# tractor_2v4.net
KiCad netlist of a schematic drawn in EAGLE
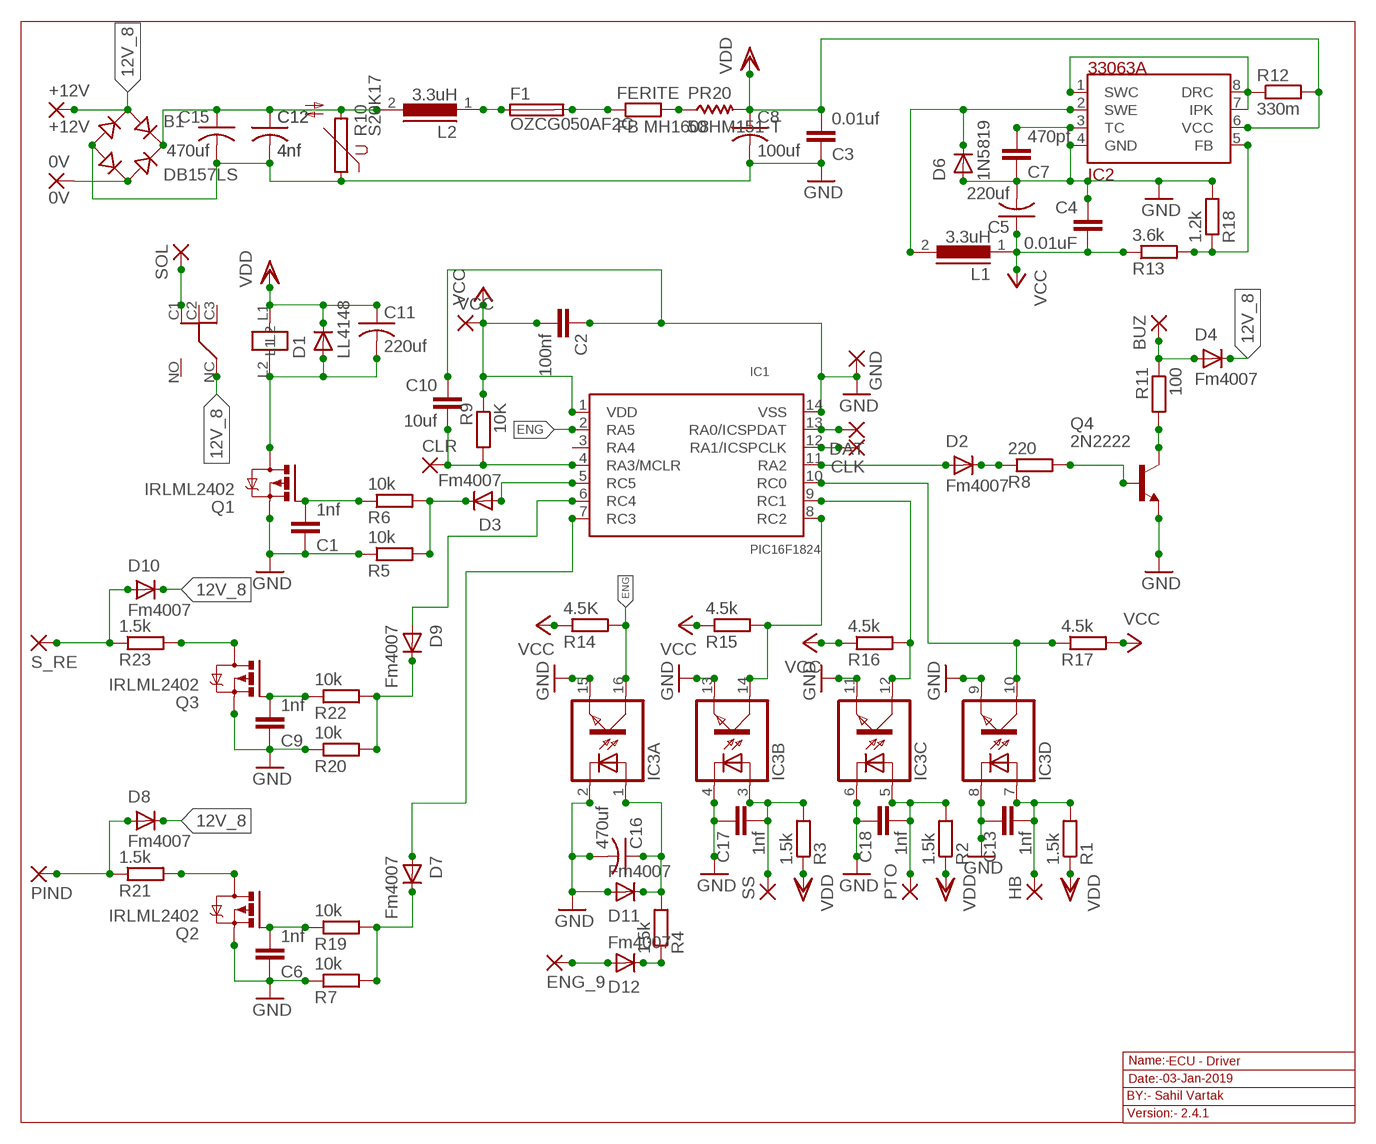
[diagram p0: schematic, sheet 1]

(export (version "E")
  (design (tool "Eeschema 10.0.6"))
  (components
    (comp (ref "+12V")
      (value "+12V")
      (footprint "eagle-import:2,54_1,1")
      (libsource (lib "eagle-import") (part "2,54/1,1"))
    )
    (comp (ref "0V")
      (value "0V")
      (footprint "eagle-import:2,54_1,1")
      (libsource (lib "eagle-import") (part "2,54/1,1"))
    )
    (comp (ref "B1")
      (value "DB157LS")
      (footprint "eagle-import:DBS")
      (libsource (lib "eagle-import") (part "DB?GS106"))
    )
    (comp (ref "BUZ")
      (value "2,54/1,1")
      (footprint "eagle-import:2,54_1,1")
      (libsource (lib "eagle-import") (part "2,54/1,1"))
    )
    (comp (ref "C1")
      (value "1nf")
      (footprint "eagle-import:C0603")
      (libsource (lib "eagle-import") (part "CC0603"))
    )
    (comp (ref "C2")
      (value "100nf")
      (footprint "eagle-import:C0603")
      (libsource (lib "eagle-import") (part "CC0603"))
    )
    (comp (ref "C3")
      (value "0.01uf")
      (footprint "eagle-import:C0603")
      (libsource (lib "eagle-import") (part "CC0603"))
    )
    (comp (ref "C4")
      (value "0.01uF")
      (footprint "eagle-import:C0603")
      (libsource (lib "eagle-import") (part "CC0603"))
    )
    (comp (ref "C5")
      (value "220uf")
      (footprint "eagle-import:C025-025X050")
      (libsource (lib "eagle-import") (part "C-US025-025X050"))
    )
    (comp (ref "C6")
      (value "1nf")
      (footprint "eagle-import:C0603")
      (libsource (lib "eagle-import") (part "CC0603"))
    )
    (comp (ref "C7")
      (value "470pf")
      (footprint "eagle-import:C0603")
      (libsource (lib "eagle-import") (part "CC0603"))
    )
    (comp (ref "C8")
      (value "100uf")
      (footprint "eagle-import:C025-025X050")
      (libsource (lib "eagle-import") (part "C-US025-025X050"))
    )
    (comp (ref "C9")
      (value "1nf")
      (footprint "eagle-import:C0603")
      (libsource (lib "eagle-import") (part "CC0603"))
    )
    (comp (ref "C10")
      (value "10uf")
      (footprint "eagle-import:C0603")
      (libsource (lib "eagle-import") (part "CC0603"))
    )
    (comp (ref "C11")
      (value "220uf")
      (footprint "eagle-import:C025-025X050")
      (libsource (lib "eagle-import") (part "C-US025-025X050"))
    )
    (comp (ref "C12")
      (value "4nf")
      (footprint "eagle-import:C050-045X075")
      (libsource (lib "eagle-import") (part "C-US050-045X075"))
    )
    (comp (ref "C13")
      (value "1nf")
      (footprint "eagle-import:C0603")
      (libsource (lib "eagle-import") (part "CC0603"))
    )
    (comp (ref "C15")
      (value "470uf")
      (footprint "eagle-import:C050-075X075")
      (libsource (lib "eagle-import") (part "resistor_C-US050-075X075"))
    )
    (comp (ref "C16")
      (value "470uf")
      (footprint "eagle-import:C050-075X075")
      (libsource (lib "eagle-import") (part "resistor_C-US050-075X075"))
    )
    (comp (ref "C17")
      (value "1nf")
      (footprint "eagle-import:C0603")
      (libsource (lib "eagle-import") (part "CC0603"))
    )
    (comp (ref "C18")
      (value "1nf")
      (footprint "eagle-import:C0603")
      (libsource (lib "eagle-import") (part "CC0603"))
    )
    (comp (ref "CLK")
      (value "1,6/0,8")
      (footprint "eagle-import:1,6_0,8")
      (libsource (lib "eagle-import") (part "1,6/0,8"))
    )
    (comp (ref "CLR")
      (value "1,6/0,8")
      (footprint "eagle-import:1,6_0,8")
      (libsource (lib "eagle-import") (part "1,6/0,8"))
    )
    (comp (ref "D1")
      (value "LL4148")
      (footprint "eagle-import:SMA-DO214AC")
      (libsource (lib "eagle-import") (part "GF1"))
    )
    (comp (ref "D2")
      (value "Fm4007")
      (footprint "eagle-import:SMA-DO214AC")
      (libsource (lib "eagle-import") (part "GF1"))
    )
    (comp (ref "D3")
      (value "Fm4007")
      (footprint "eagle-import:SMA-DO214AC")
      (libsource (lib "eagle-import") (part "GF1"))
    )
    (comp (ref "D4")
      (value "Fm4007")
      (footprint "eagle-import:SMA-DO214AC")
      (libsource (lib "eagle-import") (part "GF1"))
    )
    (comp (ref "D6")
      (value "1N5819")
      (footprint "eagle-import:SMA-DO214AC")
      (libsource (lib "eagle-import") (part "GF1"))
    )
    (comp (ref "D7")
      (value "Fm4007")
      (footprint "eagle-import:SMA-DO214AC")
      (libsource (lib "eagle-import") (part "GF1"))
    )
    (comp (ref "D8")
      (value "Fm4007")
      (footprint "eagle-import:SMA-DO214AC")
      (libsource (lib "eagle-import") (part "GF1"))
    )
    (comp (ref "D9")
      (value "Fm4007")
      (footprint "eagle-import:SMA-DO214AC")
      (libsource (lib "eagle-import") (part "GF1"))
    )
    (comp (ref "D10")
      (value "Fm4007")
      (footprint "eagle-import:SMA-DO214AC")
      (libsource (lib "eagle-import") (part "GF1"))
    )
    (comp (ref "D11")
      (value "Fm4007")
      (footprint "eagle-import:SMA-DO214AC")
      (libsource (lib "eagle-import") (part "GF1"))
    )
    (comp (ref "D12")
      (value "Fm4007")
      (footprint "eagle-import:SMA-DO214AC")
      (libsource (lib "eagle-import") (part "GF1"))
    )
    (comp (ref "DAT")
      (value "1,6/0,8")
      (footprint "eagle-import:1,6_0,8")
      (libsource (lib "eagle-import") (part "1,6/0,8"))
    )
    (comp (ref "ENG_9")
      (value "2,54/1,1")
      (footprint "eagle-import:2,54_1,1")
      (libsource (lib "eagle-import") (part "2,54/1,1"))
    )
    (comp (ref "F1")
      (value "OZCG050AF2C")
      (footprint "eagle-import:RES_FUSE")
      (libsource (lib "eagle-import") (part "RES_FUSE"))
    )
    (comp (ref "FERITE")
      (value "FB MH1608HM151-T")
      (footprint "eagle-import:R0603")
      (libsource (lib "eagle-import") (part "R-EU_R0603"))
    )
    (comp (ref "GND")
      (value "1,6/0,8")
      (footprint "eagle-import:1,6_0,8")
      (libsource (lib "eagle-import") (part "1,6/0,8"))
    )
    (comp (ref "HB")
      (value "2,54/1,1")
      (footprint "eagle-import:2,54_1,1")
      (libsource (lib "eagle-import") (part "2,54/1,1"))
    )
    (comp (ref "IC1")
      (value "PIC16F1824")
      (footprint "eagle-import:SO-14")
      (libsource (lib "eagle-import") (part "PIC16F1824"))
    )
    (comp (ref "IC2")
      (value "33063A")
      (footprint "eagle-import:D_R-PDSO-G8")
      (libsource (lib "eagle-import") (part "33063A"))
    )
    (comp (ref "IC3")
      (value "TLP283-4")
      (footprint "eagle-import:MINI-FLAT-16")
      (libsource (lib "eagle-import") (part "TLP283-4"))
    )
    (comp (ref "K2")
      (value "RL3531RL3")
      (footprint "eagle-import:RL3531")
      (libsource (lib "eagle-import") (part "RL3531RL3"))
    )
    (comp (ref "L1")
      (value "3.3uH")
      (footprint "eagle-import:82114R")
      (libsource (lib "eagle-import") (part "82114R"))
    )
    (comp (ref "L2")
      (value "3.3uH")
      (footprint "eagle-import:82114R")
      (libsource (lib "eagle-import") (part "82114R"))
    )
    (comp (ref "PIND")
      (value "2,54/1,1")
      (footprint "eagle-import:2,54_1,1")
      (libsource (lib "eagle-import") (part "2,54/1,1"))
    )
    (comp (ref "PR20")
      (value "50")
      (footprint "eagle-import:WSC2515")
      (libsource (lib "eagle-import") (part "R-US_WSC2515"))
    )
    (comp (ref "PTO")
      (value "2,54/1,1")
      (footprint "eagle-import:2,54_1,1")
      (libsource (lib "eagle-import") (part "2,54/1,1"))
    )
    (comp (ref "Q1")
      (value "IRLML2402")
      (footprint "eagle-import:MICRO3")
      (libsource (lib "eagle-import") (part "IRLML5203"))
    )
    (comp (ref "Q2")
      (value "IRLML2402")
      (footprint "eagle-import:MICRO3")
      (libsource (lib "eagle-import") (part "IRLML5203"))
    )
    (comp (ref "Q3")
      (value "IRLML2402")
      (footprint "eagle-import:MICRO3")
      (libsource (lib "eagle-import") (part "IRLML5203"))
    )
    (comp (ref "Q4")
      (value "2N2222")
      (footprint "eagle-import:TO18")
      (libsource (lib "eagle-import") (part "2N2222"))
    )
    (comp (ref "R1")
      (value "1.5k")
      (footprint "eagle-import:R0603")
      (libsource (lib "eagle-import") (part "RR0603"))
    )
    (comp (ref "R2")
      (value "1.5k")
      (footprint "eagle-import:R0603")
      (libsource (lib "eagle-import") (part "RR0603"))
    )
    (comp (ref "R3")
      (value "1.5k")
      (footprint "eagle-import:R0603")
      (libsource (lib "eagle-import") (part "RR0603"))
    )
    (comp (ref "R4")
      (value "1.5k")
      (footprint "eagle-import:R0603")
      (libsource (lib "eagle-import") (part "RR0603"))
    )
    (comp (ref "R5")
      (value "10k")
      (footprint "eagle-import:R0603")
      (libsource (lib "eagle-import") (part "RR0603"))
    )
    (comp (ref "R6")
      (value "10k")
      (footprint "eagle-import:R0603")
      (libsource (lib "eagle-import") (part "RR0603"))
    )
    (comp (ref "R7")
      (value "10k")
      (footprint "eagle-import:R0603")
      (libsource (lib "eagle-import") (part "RR0603"))
    )
    (comp (ref "R8")
      (value "220")
      (footprint "eagle-import:R0603")
      (libsource (lib "eagle-import") (part "RR0603"))
    )
    (comp (ref "R9")
      (value "10K")
      (footprint "eagle-import:R0603")
      (libsource (lib "eagle-import") (part "RR0603"))
    )
    (comp (ref "R10")
      (value "S20K17")
      (footprint "eagle-import:S14K17")
      (libsource (lib "eagle-import") (part "S14K17"))
    )
    (comp (ref "R11")
      (value "100")
      (footprint "eagle-import:R0603")
      (libsource (lib "eagle-import") (part "RR0603"))
    )
    (comp (ref "R12")
      (value "330m")
      (footprint "eagle-import:R2010")
      (libsource (lib "eagle-import") (part "RR2010"))
    )
    (comp (ref "R13")
      (value "3.6k")
      (footprint "eagle-import:R0603")
      (libsource (lib "eagle-import") (part "RR0603"))
    )
    (comp (ref "R14")
      (value "4.5K")
      (footprint "eagle-import:R0603")
      (libsource (lib "eagle-import") (part "RR0603"))
    )
    (comp (ref "R15")
      (value "4.5k")
      (footprint "eagle-import:R0603")
      (libsource (lib "eagle-import") (part "RR0603"))
    )
    (comp (ref "R16")
      (value "4.5k")
      (footprint "eagle-import:R0603")
      (libsource (lib "eagle-import") (part "RR0603"))
    )
    (comp (ref "R17")
      (value "4.5k")
      (footprint "eagle-import:R0603")
      (libsource (lib "eagle-import") (part "RR0603"))
    )
    (comp (ref "R18")
      (value "1.2k")
      (footprint "eagle-import:R0603")
      (libsource (lib "eagle-import") (part "RR0603"))
    )
    (comp (ref "R19")
      (value "10k")
      (footprint "eagle-import:R0603")
      (libsource (lib "eagle-import") (part "RR0603"))
    )
    (comp (ref "R20")
      (value "10k")
      (footprint "eagle-import:R0603")
      (libsource (lib "eagle-import") (part "RR0603"))
    )
    (comp (ref "R21")
      (value "1.5k")
      (footprint "eagle-import:R0603")
      (libsource (lib "eagle-import") (part "RR0603"))
    )
    (comp (ref "R22")
      (value "10k")
      (footprint "eagle-import:R0603")
      (libsource (lib "eagle-import") (part "RR0603"))
    )
    (comp (ref "R23")
      (value "1.5k")
      (footprint "eagle-import:R0603")
      (libsource (lib "eagle-import") (part "RR0603"))
    )
    (comp (ref "SOL")
      (value "2,54/1,1")
      (footprint "eagle-import:2,54_1,1")
      (libsource (lib "eagle-import") (part "2,54/1,1"))
    )
    (comp (ref "SS")
      (value "2,54/1,1")
      (footprint "eagle-import:2,54_1,1")
      (libsource (lib "eagle-import") (part "2,54/1,1"))
    )
    (comp (ref "S_RE")
      (value "2,54/1,1")
      (footprint "eagle-import:2,54_1,1")
      (libsource (lib "eagle-import") (part "2,54/1,1"))
    )
    (comp (ref "VCC")
      (value "1,6/0,8")
      (footprint "eagle-import:1,6_0,8")
      (libsource (lib "eagle-import") (part "1,6/0,8"))
    )
  )
  (nets
    (net (code "1") (name "12V_8") (class "Default")
      (node (ref "+12V") (pin "1") (pinfunction "P_1") (pintype "passive"))
      (node (ref "B1") (pin "AC1") (pinfunction "AC1_AC1") (pintype "passive"))
      (node (ref "D10") (pin "K") (pinfunction "C_K") (pintype "passive"))
      (node (ref "D4") (pin "K") (pinfunction "C_K") (pintype "passive"))
      (node (ref "D8") (pin "K") (pinfunction "C_K") (pintype "passive"))
      (node (ref "K2") (pin "NC") (pinfunction "NC_NC") (pintype "output"))
    )
    (net (code "2") (name "ENG") (class "Default")
      (node (ref "IC1") (pin "2") (pinfunction "RA5_2") (pintype "bidirectional"))
      (node (ref "IC3") (pin "16") (pinfunction "COL_16") (pintype "passive"))
      (node (ref "R14") (pin "2") (pinfunction "2_2") (pintype "passive"))
    )
    (net (code "3") (name "GND") (class "Default")
      (node (ref "B1") (pin "-") (pinfunction "-_-") (pintype "passive"))
      (node (ref "C1") (pin "1") (pinfunction "1_1") (pintype "passive"))
      (node (ref "C10") (pin "1") (pinfunction "1_1") (pintype "passive"))
      (node (ref "C12") (pin "2") (pinfunction "2_2") (pintype "passive"))
      (node (ref "C13") (pin "1") (pinfunction "1_1") (pintype "passive"))
      (node (ref "C15") (pin "2") (pinfunction "2_2") (pintype "passive"))
      (node (ref "C16") (pin "2") (pinfunction "2_2") (pintype "passive"))
      (node (ref "C17") (pin "1") (pinfunction "1_1") (pintype "passive"))
      (node (ref "C18") (pin "1") (pinfunction "1_1") (pintype "passive"))
      (node (ref "C2") (pin "1") (pinfunction "1_1") (pintype "passive"))
      (node (ref "C3") (pin "1") (pinfunction "1_1") (pintype "passive"))
      (node (ref "C4") (pin "1") (pinfunction "1_1") (pintype "passive"))
      (node (ref "C5") (pin "2") (pinfunction "2_2") (pintype "passive"))
      (node (ref "C6") (pin "1") (pinfunction "1_1") (pintype "passive"))
      (node (ref "C7") (pin "1") (pinfunction "1_1") (pintype "passive"))
      (node (ref "C8") (pin "2") (pinfunction "2_2") (pintype "passive"))
      (node (ref "C9") (pin "1") (pinfunction "1_1") (pintype "passive"))
      (node (ref "D11") (pin "A") (pinfunction "A_A") (pintype "passive"))
      (node (ref "D6") (pin "A") (pinfunction "A_A") (pintype "passive"))
      (node (ref "GND") (pin "1") (pinfunction "P_1") (pintype "passive"))
      (node (ref "IC1") (pin "14") (pinfunction "VSS_14") (pintype "bidirectional"))
      (node (ref "IC2") (pin "4") (pinfunction "GND_4") (pintype "bidirectional"))
      (node (ref "IC3") (pin "11") (pinfunction "EMIT_11") (pintype "passive"))
      (node (ref "IC3") (pin "13") (pinfunction "EMIT_13") (pintype "passive"))
      (node (ref "IC3") (pin "15") (pinfunction "EMIT_15") (pintype "passive"))
      (node (ref "IC3") (pin "2") (pinfunction "C_2") (pintype "passive"))
      (node (ref "IC3") (pin "4") (pinfunction "C_4") (pintype "passive"))
      (node (ref "IC3") (pin "6") (pinfunction "C_6") (pintype "passive"))
      (node (ref "IC3") (pin "8") (pinfunction "C_8") (pintype "passive"))
      (node (ref "IC3") (pin "9") (pinfunction "EMIT_9") (pintype "passive"))
      (node (ref "Q1") (pin "2") (pinfunction "S_2") (pintype "passive"))
      (node (ref "Q2") (pin "2") (pinfunction "S_2") (pintype "passive"))
      (node (ref "Q3") (pin "2") (pinfunction "S_2") (pintype "passive"))
      (node (ref "Q4") (pin "1") (pinfunction "E_1") (pintype "passive"))
      (node (ref "R10") (pin "1") (pinfunction "1_1") (pintype "passive"))
      (node (ref "R18") (pin "2") (pinfunction "2_2") (pintype "passive"))
      (node (ref "R20") (pin "1") (pinfunction "1_1") (pintype "passive"))
      (node (ref "R5") (pin "1") (pinfunction "1_1") (pintype "passive"))
      (node (ref "R7") (pin "1") (pinfunction "1_1") (pintype "passive"))
    )
    (net (code "4") (name "Net-(0V-P)") (class "Default")
      (node (ref "0V") (pin "1") (pinfunction "P_1") (pintype "passive"))
      (node (ref "B1") (pin "AC2") (pinfunction "AC2_AC2") (pintype "passive"))
    )
    (net (code "5") (name "Net-(B1-Pad+)") (class "Default")
      (node (ref "B1") (pin "+") (pinfunction "+_+") (pintype "passive"))
      (node (ref "C12") (pin "1") (pinfunction "1_1") (pintype "passive"))
      (node (ref "C15") (pin "1") (pinfunction "1_1") (pintype "passive"))
      (node (ref "L2") (pin "2") (pinfunction "2_2") (pintype "passive"))
      (node (ref "R10") (pin "2") (pinfunction "2_2") (pintype "passive"))
    )
    (net (code "6") (name "Net-(BUZ-P)") (class "Default")
      (node (ref "BUZ") (pin "1") (pinfunction "P_1") (pintype "passive"))
      (node (ref "D4") (pin "A") (pinfunction "A_A") (pintype "passive"))
      (node (ref "R11") (pin "1") (pinfunction "1_1") (pintype "passive"))
    )
    (net (code "7") (name "Net-(CLK-P)") (class "Default")
      (node (ref "CLK") (pin "1") (pinfunction "P_1") (pintype "passive"))
      (node (ref "IC1") (pin "12") (pinfunction "RA1/ICSPCLK_12") (pintype "bidirectional"))
    )
    (net (code "8") (name "Net-(CLR-P)") (class "Default")
      (node (ref "C10") (pin "2") (pinfunction "2_2") (pintype "passive"))
      (node (ref "CLR") (pin "1") (pinfunction "P_1") (pintype "passive"))
      (node (ref "IC1") (pin "4") (pinfunction "RA3/MCLR_4") (pintype "bidirectional"))
      (node (ref "R9") (pin "2") (pinfunction "2_2") (pintype "passive"))
    )
    (net (code "9") (name "Net-(D2-C)") (class "Default")
      (node (ref "D2") (pin "K") (pinfunction "C_K") (pintype "passive"))
      (node (ref "R8") (pin "1") (pinfunction "1_1") (pintype "passive"))
    )
    (net (code "10") (name "Net-(D3-C)") (class "Default")
      (node (ref "D3") (pin "K") (pinfunction "C_K") (pintype "passive"))
      (node (ref "R5") (pin "2") (pinfunction "2_2") (pintype "passive"))
      (node (ref "R6") (pin "2") (pinfunction "2_2") (pintype "passive"))
    )
    (net (code "11") (name "Net-(D6-C)") (class "Default")
      (node (ref "D6") (pin "K") (pinfunction "C_K") (pintype "passive"))
      (node (ref "IC2") (pin "2") (pinfunction "SWE_2") (pintype "bidirectional"))
      (node (ref "L1") (pin "2") (pinfunction "2_2") (pintype "passive"))
    )
    (net (code "12") (name "Net-(D7-C)") (class "Default")
      (node (ref "D7") (pin "K") (pinfunction "C_K") (pintype "passive"))
      (node (ref "R19") (pin "2") (pinfunction "2_2") (pintype "passive"))
      (node (ref "R7") (pin "2") (pinfunction "2_2") (pintype "passive"))
    )
    (net (code "13") (name "Net-(D9-C)") (class "Default")
      (node (ref "D9") (pin "K") (pinfunction "C_K") (pintype "passive"))
      (node (ref "R20") (pin "2") (pinfunction "2_2") (pintype "passive"))
      (node (ref "R22") (pin "2") (pinfunction "2_2") (pintype "passive"))
    )
    (net (code "14") (name "Net-(D11-C)") (class "Default")
      (node (ref "C16") (pin "1") (pinfunction "1_1") (pintype "passive"))
      (node (ref "D11") (pin "K") (pinfunction "C_K") (pintype "passive"))
      (node (ref "IC3") (pin "1") (pinfunction "A_1") (pintype "passive"))
      (node (ref "R4") (pin "2") (pinfunction "2_2") (pintype "passive"))
    )
    (net (code "15") (name "Net-(D12-C)") (class "Default")
      (node (ref "D12") (pin "K") (pinfunction "C_K") (pintype "passive"))
      (node (ref "R4") (pin "1") (pinfunction "1_1") (pintype "passive"))
    )
    (net (code "16") (name "Net-(DAT-P)") (class "Default")
      (node (ref "DAT") (pin "1") (pinfunction "P_1") (pintype "passive"))
      (node (ref "IC1") (pin "13") (pinfunction "RA0/ICSPDAT_13") (pintype "bidirectional"))
    )
    (net (code "17") (name "Net-(ENG_9-P)") (class "Default")
      (node (ref "D12") (pin "A") (pinfunction "A_A") (pintype "passive"))
      (node (ref "ENG_9") (pin "1") (pinfunction "P_1") (pintype "passive"))
    )
    (net (code "18") (name "Net-(F1-3)") (class "Default")
      (node (ref "F1") (pin "1") (pinfunction "3_1") (pintype "passive"))
      (node (ref "L2") (pin "1") (pinfunction "1_1") (pintype "passive"))
    )
    (net (code "19") (name "Net-(F1-4)") (class "Default")
      (node (ref "F1") (pin "2") (pinfunction "4_2") (pintype "passive"))
      (node (ref "FERITE") (pin "1") (pinfunction "1_1") (pintype "passive"))
    )
    (net (code "20") (name "Net-(FERITE-Pad2)") (class "Default")
      (node (ref "FERITE") (pin "2") (pinfunction "2_2") (pintype "passive"))
      (node (ref "PR20") (pin "1") (pinfunction "1_1") (pintype "passive"))
    )
    (net (code "21") (name "Net-(HB-P)") (class "Default")
      (node (ref "C13") (pin "2") (pinfunction "2_2") (pintype "passive"))
      (node (ref "HB") (pin "1") (pinfunction "P_1") (pintype "passive"))
      (node (ref "IC3") (pin "7") (pinfunction "A_7") (pintype "passive"))
      (node (ref "R1") (pin "2") (pinfunction "2_2") (pintype "passive"))
    )
    (net (code "22") (name "Net-(IC1-RA2)") (class "Default")
      (node (ref "D2") (pin "A") (pinfunction "A_A") (pintype "passive"))
      (node (ref "IC1") (pin "11") (pinfunction "RA2_11") (pintype "bidirectional"))
    )
    (net (code "23") (name "Net-(IC1-RC0)") (class "Default")
      (node (ref "IC1") (pin "10") (pinfunction "RC0_10") (pintype "bidirectional"))
      (node (ref "IC3") (pin "10") (pinfunction "COL_10") (pintype "passive"))
      (node (ref "R17") (pin "1") (pinfunction "1_1") (pintype "passive"))
    )
    (net (code "24") (name "Net-(IC1-RC1)") (class "Default")
      (node (ref "IC1") (pin "9") (pinfunction "RC1_9") (pintype "bidirectional"))
      (node (ref "IC3") (pin "12") (pinfunction "COL_12") (pintype "passive"))
      (node (ref "R16") (pin "2") (pinfunction "2_2") (pintype "passive"))
    )
    (net (code "25") (name "Net-(IC1-RC2)") (class "Default")
      (node (ref "IC1") (pin "8") (pinfunction "RC2_8") (pintype "bidirectional"))
      (node (ref "IC3") (pin "14") (pinfunction "COL_14") (pintype "passive"))
      (node (ref "R15") (pin "2") (pinfunction "2_2") (pintype "passive"))
    )
    (net (code "26") (name "Net-(IC1-RC3)") (class "Default")
      (node (ref "D7") (pin "A") (pinfunction "A_A") (pintype "passive"))
      (node (ref "IC1") (pin "7") (pinfunction "RC3_7") (pintype "bidirectional"))
    )
    (net (code "27") (name "Net-(IC1-RC4)") (class "Default")
      (node (ref "D9") (pin "A") (pinfunction "A_A") (pintype "passive"))
      (node (ref "IC1") (pin "6") (pinfunction "RC4_6") (pintype "bidirectional"))
    )
    (net (code "28") (name "Net-(IC1-RC5)") (class "Default")
      (node (ref "D3") (pin "A") (pinfunction "A_A") (pintype "passive"))
      (node (ref "IC1") (pin "5") (pinfunction "RC5_5") (pintype "bidirectional"))
    )
    (net (code "29") (name "Net-(IC2-DRC)") (class "Default")
      (node (ref "IC2") (pin "1") (pinfunction "SWC_1") (pintype "bidirectional"))
      (node (ref "IC2") (pin "7") (pinfunction "IPK_7") (pintype "bidirectional"))
      (node (ref "IC2") (pin "8") (pinfunction "DRC_8") (pintype "bidirectional"))
      (node (ref "R12") (pin "1") (pinfunction "1_1") (pintype "passive"))
    )
    (net (code "30") (name "Net-(IC2-FB)") (class "Default")
      (node (ref "IC2") (pin "5") (pinfunction "FB_5") (pintype "bidirectional"))
      (node (ref "R13") (pin "2") (pinfunction "2_2") (pintype "passive"))
      (node (ref "R18") (pin "1") (pinfunction "1_1") (pintype "passive"))
    )
    (net (code "31") (name "Net-(IC2-TC)") (class "Default")
      (node (ref "C7") (pin "2") (pinfunction "2_2") (pintype "passive"))
      (node (ref "IC2") (pin "3") (pinfunction "TC_3") (pintype "bidirectional"))
    )
    (net (code "32") (name "Net-(IC3B-A)") (class "Default")
      (node (ref "C17") (pin "2") (pinfunction "2_2") (pintype "passive"))
      (node (ref "IC3") (pin "3") (pinfunction "A_3") (pintype "passive"))
      (node (ref "R3") (pin "2") (pinfunction "2_2") (pintype "passive"))
      (node (ref "SS") (pin "1") (pinfunction "P_1") (pintype "passive"))
    )
    (net (code "33") (name "Net-(IC3C-A)") (class "Default")
      (node (ref "C18") (pin "2") (pinfunction "2_2") (pintype "passive"))
      (node (ref "IC3") (pin "5") (pinfunction "A_5") (pintype "passive"))
      (node (ref "PTO") (pin "1") (pinfunction "P_1") (pintype "passive"))
      (node (ref "R2") (pin "2") (pinfunction "2_2") (pintype "passive"))
    )
    (net (code "34") (name "Net-(PIND-P)") (class "Default")
      (node (ref "D8") (pin "A") (pinfunction "A_A") (pintype "passive"))
      (node (ref "PIND") (pin "1") (pinfunction "P_1") (pintype "passive"))
      (node (ref "R21") (pin "1") (pinfunction "1_1") (pintype "passive"))
    )
    (net (code "35") (name "Net-(Q1-D)") (class "Default")
      (node (ref "C11") (pin "2") (pinfunction "2_2") (pintype "passive"))
      (node (ref "D1") (pin "A") (pinfunction "A_A") (pintype "passive"))
      (node (ref "K2") (pin "L2") (pinfunction "L2_L2") (pintype "bidirectional"))
      (node (ref "Q1") (pin "3") (pinfunction "D_3") (pintype "passive"))
    )
    (net (code "36") (name "Net-(Q1-G)") (class "Default")
      (node (ref "C1") (pin "2") (pinfunction "2_2") (pintype "passive"))
      (node (ref "Q1") (pin "1") (pinfunction "G_1") (pintype "passive"))
      (node (ref "R6") (pin "1") (pinfunction "1_1") (pintype "passive"))
    )
    (net (code "37") (name "Net-(Q2-D)") (class "Default")
      (node (ref "Q2") (pin "3") (pinfunction "D_3") (pintype "passive"))
      (node (ref "R21") (pin "2") (pinfunction "2_2") (pintype "passive"))
    )
    (net (code "38") (name "Net-(Q2-G)") (class "Default")
      (node (ref "C6") (pin "2") (pinfunction "2_2") (pintype "passive"))
      (node (ref "Q2") (pin "1") (pinfunction "G_1") (pintype "passive"))
      (node (ref "R19") (pin "1") (pinfunction "1_1") (pintype "passive"))
    )
    (net (code "39") (name "Net-(Q3-D)") (class "Default")
      (node (ref "Q3") (pin "3") (pinfunction "D_3") (pintype "passive"))
      (node (ref "R23") (pin "2") (pinfunction "2_2") (pintype "passive"))
    )
    (net (code "40") (name "Net-(Q3-G)") (class "Default")
      (node (ref "C9") (pin "2") (pinfunction "2_2") (pintype "passive"))
      (node (ref "Q3") (pin "1") (pinfunction "G_1") (pintype "passive"))
      (node (ref "R22") (pin "1") (pinfunction "1_1") (pintype "passive"))
    )
    (net (code "41") (name "Net-(Q4-B)") (class "Default")
      (node (ref "Q4") (pin "2") (pinfunction "B_2") (pintype "passive"))
      (node (ref "R8") (pin "2") (pinfunction "2_2") (pintype "passive"))
    )
    (net (code "42") (name "Net-(Q4-C)") (class "Default")
      (node (ref "Q4") (pin "3") (pinfunction "C_3") (pintype "passive"))
      (node (ref "R11") (pin "2") (pinfunction "2_2") (pintype "passive"))
    )
    (net (code "43") (name "Net-(SOL-P)") (class "Default")
      (node (ref "K2") (pin "C1") (pinfunction "C1_C1") (pintype "bidirectional"))
      (node (ref "SOL") (pin "1") (pinfunction "P_1") (pintype "passive"))
    )
    (net (code "44") (name "Net-(S_RE-P)") (class "Default")
      (node (ref "D10") (pin "A") (pinfunction "A_A") (pintype "passive"))
      (node (ref "R23") (pin "1") (pinfunction "1_1") (pintype "passive"))
      (node (ref "S_RE") (pin "1") (pinfunction "P_1") (pintype "passive"))
    )
    (net (code "45") (name "VCC") (class "Default")
      (node (ref "C2") (pin "2") (pinfunction "2_2") (pintype "passive"))
      (node (ref "C4") (pin "2") (pinfunction "2_2") (pintype "passive"))
      (node (ref "C5") (pin "1") (pinfunction "1_1") (pintype "passive"))
      (node (ref "IC1") (pin "1") (pinfunction "VDD_1") (pintype "bidirectional"))
      (node (ref "L1") (pin "1") (pinfunction "1_1") (pintype "passive"))
      (node (ref "R13") (pin "1") (pinfunction "1_1") (pintype "passive"))
      (node (ref "R14") (pin "1") (pinfunction "1_1") (pintype "passive"))
      (node (ref "R15") (pin "1") (pinfunction "1_1") (pintype "passive"))
      (node (ref "R16") (pin "1") (pinfunction "1_1") (pintype "passive"))
      (node (ref "R17") (pin "2") (pinfunction "2_2") (pintype "passive"))
      (node (ref "R9") (pin "1") (pinfunction "1_1") (pintype "passive"))
      (node (ref "VCC") (pin "1") (pinfunction "P_1") (pintype "passive"))
    )
    (net (code "46") (name "VDD") (class "Default")
      (node (ref "C11") (pin "1") (pinfunction "1_1") (pintype "passive"))
      (node (ref "C3") (pin "2") (pinfunction "2_2") (pintype "passive"))
      (node (ref "C8") (pin "1") (pinfunction "1_1") (pintype "passive"))
      (node (ref "D1") (pin "K") (pinfunction "C_K") (pintype "passive"))
      (node (ref "IC2") (pin "6") (pinfunction "VCC_6") (pintype "bidirectional"))
      (node (ref "K2") (pin "L1") (pinfunction "L1_L1") (pintype "bidirectional"))
      (node (ref "PR20") (pin "2") (pinfunction "2_2") (pintype "passive"))
      (node (ref "R1") (pin "1") (pinfunction "1_1") (pintype "passive"))
      (node (ref "R12") (pin "2") (pinfunction "2_2") (pintype "passive"))
      (node (ref "R2") (pin "1") (pinfunction "1_1") (pintype "passive"))
      (node (ref "R3") (pin "1") (pinfunction "1_1") (pintype "passive"))
    )
    (net (code "47") (name "unconnected-(IC1-RA4-Pad3)") (class "Default")
      (node (ref "IC1") (pin "3") (pinfunction "RA4_3") (pintype "bidirectional"))
    )
    (net (code "48") (name "unconnected-(K2-PadC2)") (class "Default")
      (node (ref "K2") (pin "C2") (pinfunction "C2_C2") (pintype "bidirectional"))
    )
    (net (code "49") (name "unconnected-(K2-PadC3)") (class "Default")
      (node (ref "K2") (pin "C3") (pinfunction "C3_C3") (pintype "bidirectional"))
    )
    (net (code "50") (name "unconnected-(K2-PadNO)") (class "Default")
      (node (ref "K2") (pin "NO") (pinfunction "NO_NO") (pintype "output"))
    )
  )
)
